# v1.net
KiCad netlist of a schematic drawn in EAGLE
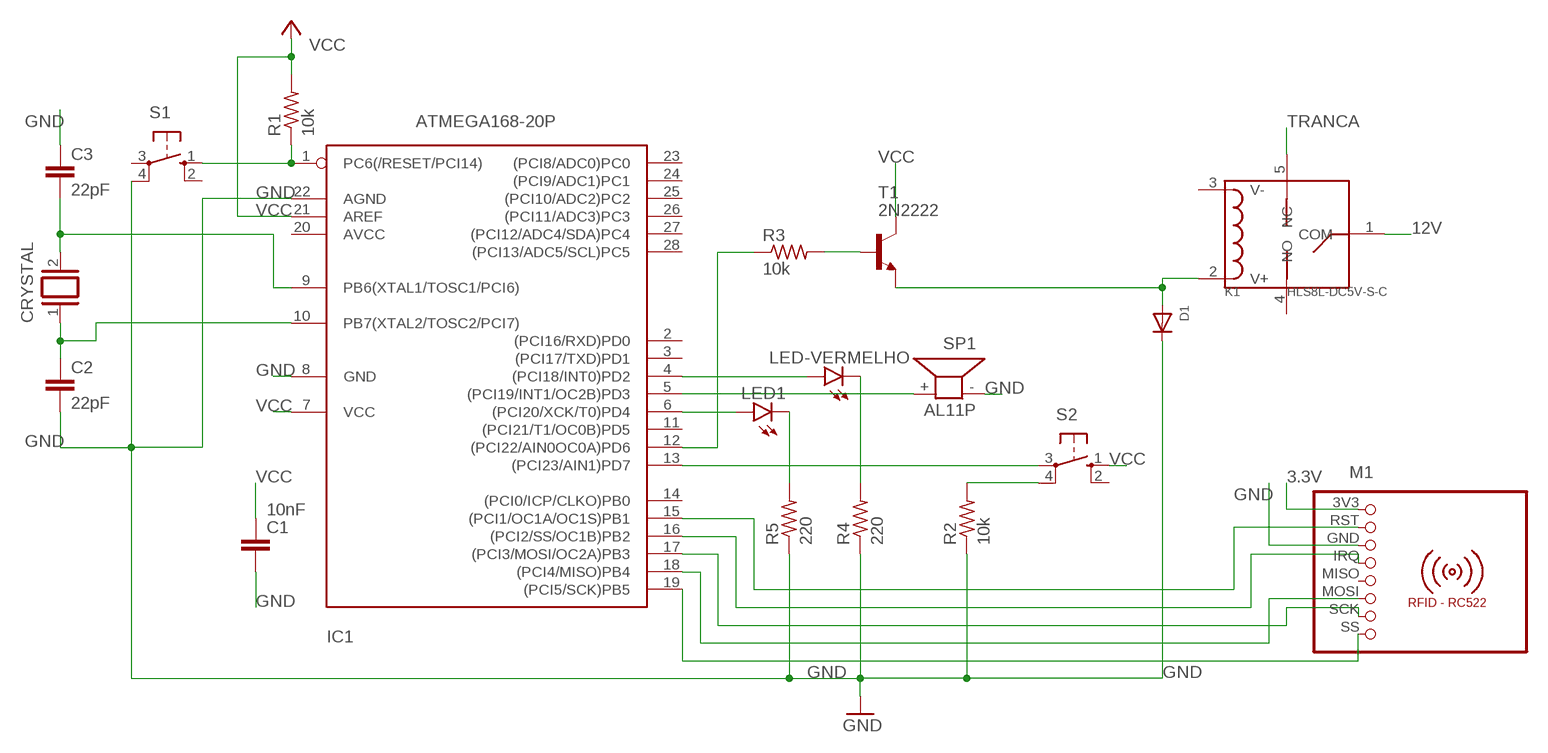
[diagram p0: schematic, sheet 1]

(export (version "E")
  (design (tool "Eeschema 10.0.6"))
  (components
    (comp (ref "C1")
      (value "10nF")
      (footprint "eagle-import:C025-025X050")
      (libsource (lib "eagle-import") (part "C-EU025-025X050"))
    )
    (comp (ref "C2")
      (value "22pF")
      (footprint "eagle-import:C025-025X050")
      (libsource (lib "eagle-import") (part "C-EU025-025X050"))
    )
    (comp (ref "C3")
      (value "22pF")
      (footprint "eagle-import:C025-025X050")
      (libsource (lib "eagle-import") (part "C-EU025-025X050"))
    )
    (comp (ref "CRYSTAL")
      (value "XTAL/S")
      (footprint "eagle-import:QS")
      (libsource (lib "eagle-import") (part "XTAL/S"))
    )
    (comp (ref "D1")
      (value "DIODEDO-1N4148")
      (footprint "eagle-import:DO-1N4148")
      (libsource (lib "eagle-import") (part "DIODEDO-1N4148"))
    )
    (comp (ref "IC1")
      (value "ATMEGA168-20P")
      (footprint "eagle-import:DIL28-3")
      (libsource (lib "eagle-import") (part "ATMEGA168P-20"))
    )
    (comp (ref "K1")
      (value "HLS8L-DC5V-S-C")
      (footprint "eagle-import:REY5-19.0X15.0X15.0MM")
      (libsource (lib "eagle-import") (part "RELAY-HLS8L-DC5V-S-C(5P-19X15MM)"))
    )
    (comp (ref "LED-VERMELHO")
      (value "LED5MM")
      (footprint "eagle-import:LED5MM")
      (libsource (lib "eagle-import") (part "LED5MM"))
    )
    (comp (ref "LED1")
      (value "LED5MM")
      (footprint "eagle-import:LED5MM")
      (libsource (lib "eagle-import") (part "LED5MM"))
    )
    (comp (ref "M1")
      (value "RFID-RC522")
      (footprint "eagle-import:RFID-RC522")
      (libsource (lib "eagle-import") (part "RFID-RC522"))
    )
    (comp (ref "R1")
      (value "10k")
      (footprint "eagle-import:0204_7")
      (libsource (lib "eagle-import") (part "R-US_0204/7"))
    )
    (comp (ref "R2")
      (value "10k")
      (footprint "eagle-import:0204_7")
      (libsource (lib "eagle-import") (part "R-US_0204/7"))
    )
    (comp (ref "R3")
      (value "10k")
      (footprint "eagle-import:0204_7")
      (libsource (lib "eagle-import") (part "R-US_0204/7"))
    )
    (comp (ref "R4")
      (value "220")
      (footprint "eagle-import:0204_7")
      (libsource (lib "eagle-import") (part "R-US_0204/7"))
    )
    (comp (ref "R5")
      (value "220")
      (footprint "eagle-import:0204_7")
      (libsource (lib "eagle-import") (part "R-US_0204/7"))
    )
    (comp (ref "S1")
      (value "10-XX")
      (footprint "eagle-import:B3F-10XX")
      (fields (field (name "MPN") "B3F-1000"))
      (libsource (lib "eagle-import") (part "10-XX"))
    )
    (comp (ref "S2")
      (value "10-XX")
      (footprint "eagle-import:B3F-10XX")
      (fields (field (name "MPN") "B3F-1000"))
      (libsource (lib "eagle-import") (part "10-XX"))
    )
    (comp (ref "SP1")
      (value "AL11P")
      (footprint "eagle-import:AL11P")
      (libsource (lib "eagle-import") (part "AL11P"))
    )
    (comp (ref "T1")
      (value "2N2222")
      (footprint "eagle-import:TO92-EBC-OVAL")
      (libsource (lib "eagle-import") (part "2N2222"))
    )
  )
  (nets
    (net (code "1") (name "/3.3V") (class "Default")
      (node (ref "M1") (pin "3V3") (pinfunction "1_3V3") (pintype "passive"))
    )
    (net (code "2") (name "/12V") (class "Default")
      (node (ref "K1") (pin "1") (pinfunction "COM_1") (pintype "bidirectional"))
    )
    (net (code "3") (name "/TRANCA") (class "Default")
      (node (ref "K1") (pin "5") (pinfunction "NC_5") (pintype "bidirectional"))
    )
    (net (code "4") (name "GND") (class "Default")
      (node (ref "C1") (pin "2") (pinfunction "2_2") (pintype "passive"))
      (node (ref "C2") (pin "2") (pinfunction "2_2") (pintype "passive"))
      (node (ref "C3") (pin "1") (pinfunction "1_1") (pintype "passive"))
      (node (ref "D1") (pin "C") (pinfunction "C_C") (pintype "passive"))
      (node (ref "IC1") (pin "22") (pinfunction "AGND_22") (pintype "bidirectional"))
      (node (ref "IC1") (pin "8") (pinfunction "GND_8") (pintype "bidirectional"))
      (node (ref "M1") (pin "GND") (pinfunction "3_GND") (pintype "passive"))
      (node (ref "R2") (pin "1") (pinfunction "1_1") (pintype "passive"))
      (node (ref "R4") (pin "1") (pinfunction "1_1") (pintype "passive"))
      (node (ref "R5") (pin "1") (pinfunction "1_1") (pintype "passive"))
      (node (ref "S1") (pin "4") (pinfunction "P1_4") (pintype "passive"))
      (node (ref "SP1") (pin "-") (pinfunction "1_-") (pintype "passive"))
    )
    (net (code "5") (name "Net-(IC1-(PCI1{slash}OC1A{slash}OC1S)PB1)") (class "Default")
      (node (ref "IC1") (pin "15") (pinfunction "(PCI1/OC1A/OC1S)PB1_15") (pintype "bidirectional"))
      (node (ref "M1") (pin "RST") (pinfunction "2_RST") (pintype "passive"))
    )
    (net (code "6") (name "Net-(IC1-(PCI2{slash}SS{slash}OC1B)PB2)") (class "Default")
      (node (ref "IC1") (pin "16") (pinfunction "(PCI2/SS/OC1B)PB2_16") (pintype "bidirectional"))
      (node (ref "M1") (pin "IRQ") (pinfunction "4_IRQ") (pintype "passive"))
    )
    (net (code "7") (name "Net-(IC1-(PCI3{slash}MOSI{slash}OC2A)PB3)") (class "Default")
      (node (ref "IC1") (pin "17") (pinfunction "(PCI3/MOSI/OC2A)PB3_17") (pintype "bidirectional"))
      (node (ref "M1") (pin "SCK") (pinfunction "7_SCK") (pintype "passive"))
    )
    (net (code "8") (name "Net-(IC1-(PCI4{slash}MISO)PB4)") (class "Default")
      (node (ref "IC1") (pin "18") (pinfunction "(PCI4/MISO)PB4_18") (pintype "bidirectional"))
      (node (ref "M1") (pin "MOSI") (pinfunction "6_MOSI") (pintype "passive"))
    )
    (net (code "9") (name "Net-(IC1-(PCI5{slash}SCK)PB5)") (class "Default")
      (node (ref "IC1") (pin "19") (pinfunction "(PCI5/SCK)PB5_19") (pintype "bidirectional"))
      (node (ref "M1") (pin "SS") (pinfunction "8_SS") (pintype "passive"))
    )
    (net (code "10") (name "Net-(IC1-(PCI18{slash}INT0)PD2)") (class "Default")
      (node (ref "IC1") (pin "4") (pinfunction "(PCI18/INT0)PD2_4") (pintype "bidirectional"))
      (node (ref "LED-VERMELHO") (pin "A") (pinfunction "A_A") (pintype "passive"))
    )
    (net (code "11") (name "Net-(IC1-(PCI19{slash}INT1{slash}OC2B)PD3)") (class "Default")
      (node (ref "IC1") (pin "5") (pinfunction "(PCI19/INT1/OC2B)PD3_5") (pintype "bidirectional"))
      (node (ref "SP1") (pin "+") (pinfunction "2_+") (pintype "passive"))
    )
    (net (code "12") (name "Net-(IC1-(PCI20{slash}XCK{slash}T0)PD4)") (class "Default")
      (node (ref "IC1") (pin "6") (pinfunction "(PCI20/XCK/T0)PD4_6") (pintype "bidirectional"))
      (node (ref "LED1") (pin "A") (pinfunction "A_A") (pintype "passive"))
    )
    (net (code "13") (name "Net-(IC1-(PCI22{slash}AIN0OC0A)PD6)") (class "Default")
      (node (ref "IC1") (pin "12") (pinfunction "(PCI22/AIN0OC0A)PD6_12") (pintype "bidirectional"))
      (node (ref "R3") (pin "1") (pinfunction "1_1") (pintype "passive"))
    )
    (net (code "14") (name "Net-(IC1-(PCI23{slash}AIN1)PD7)") (class "Default")
      (node (ref "IC1") (pin "13") (pinfunction "(PCI23/AIN1)PD7_13") (pintype "bidirectional"))
      (node (ref "S2") (pin "3") (pinfunction "P_3") (pintype "passive"))
    )
    (net (code "15") (name "Net-(IC1-PB6(XTAL1{slash}TOSC1{slash}PCI6))") (class "Default")
      (node (ref "C3") (pin "2") (pinfunction "2_2") (pintype "passive"))
      (node (ref "CRYSTAL") (pin "2") (pinfunction "2_2") (pintype "passive"))
      (node (ref "IC1") (pin "9") (pinfunction "PB6(XTAL1/TOSC1/PCI6)_9") (pintype "bidirectional"))
    )
    (net (code "16") (name "Net-(IC1-PB7(XTAL2{slash}TOSC2{slash}PCI7))") (class "Default")
      (node (ref "C2") (pin "1") (pinfunction "1_1") (pintype "passive"))
      (node (ref "CRYSTAL") (pin "1") (pinfunction "1_1") (pintype "passive"))
      (node (ref "IC1") (pin "10") (pinfunction "PB7(XTAL2/TOSC2/PCI7)_10") (pintype "bidirectional"))
    )
    (net (code "17") (name "Net-(IC1-PC6({slash}RESET{slash}PCI14))") (class "Default")
      (node (ref "IC1") (pin "1") (pinfunction "PC6(/RESET/PCI14)_1") (pintype "bidirectional"))
      (node (ref "R1") (pin "1") (pinfunction "1_1") (pintype "passive"))
      (node (ref "S1") (pin "1") (pinfunction "S_1") (pintype "passive"))
    )
    (net (code "18") (name "Net-(K1-V+)") (class "Default")
      (node (ref "D1") (pin "A") (pinfunction "A_A") (pintype "passive"))
      (node (ref "K1") (pin "2") (pinfunction "V+_2") (pintype "bidirectional"))
      (node (ref "T1") (pin "E") (pinfunction "E_E") (pintype "passive"))
    )
    (net (code "19") (name "Net-(LED-VERMELHO-C)") (class "Default")
      (node (ref "LED-VERMELHO") (pin "K") (pinfunction "C_K") (pintype "passive"))
      (node (ref "R4") (pin "2") (pinfunction "2_2") (pintype "passive"))
    )
    (net (code "20") (name "Net-(LED1-C)") (class "Default")
      (node (ref "LED1") (pin "K") (pinfunction "C_K") (pintype "passive"))
      (node (ref "R5") (pin "2") (pinfunction "2_2") (pintype "passive"))
    )
    (net (code "21") (name "Net-(R3-Pad2)") (class "Default")
      (node (ref "R3") (pin "2") (pinfunction "2_2") (pintype "passive"))
      (node (ref "T1") (pin "B") (pinfunction "B_B") (pintype "passive"))
    )
    (net (code "22") (name "Net-(S2-P1)") (class "Default")
      (node (ref "R2") (pin "2") (pinfunction "2_2") (pintype "passive"))
      (node (ref "S2") (pin "4") (pinfunction "P1_4") (pintype "passive"))
    )
    (net (code "23") (name "VCC") (class "Default")
      (node (ref "C1") (pin "1") (pinfunction "1_1") (pintype "passive"))
      (node (ref "IC1") (pin "21") (pinfunction "AREF_21") (pintype "bidirectional"))
      (node (ref "IC1") (pin "7") (pinfunction "VCC_7") (pintype "bidirectional"))
      (node (ref "R1") (pin "2") (pinfunction "2_2") (pintype "passive"))
      (node (ref "S2") (pin "1") (pinfunction "S_1") (pintype "passive"))
      (node (ref "T1") (pin "C") (pinfunction "C_C") (pintype "passive"))
    )
    (net (code "24") (name "unconnected-(IC1-(PCI0{slash}ICP{slash}CLKO)PB0-Pad14)") (class "Default")
      (node (ref "IC1") (pin "14") (pinfunction "(PCI0/ICP/CLKO)PB0_14") (pintype "bidirectional"))
    )
    (net (code "25") (name "unconnected-(IC1-(PCI8{slash}ADC0)PC0-Pad23)") (class "Default")
      (node (ref "IC1") (pin "23") (pinfunction "(PCI8/ADC0)PC0_23") (pintype "bidirectional"))
    )
    (net (code "26") (name "unconnected-(IC1-(PCI9{slash}ADC1)PC1-Pad24)") (class "Default")
      (node (ref "IC1") (pin "24") (pinfunction "(PCI9/ADC1)PC1_24") (pintype "bidirectional"))
    )
    (net (code "27") (name "unconnected-(IC1-(PCI10{slash}ADC2)PC2-Pad25)") (class "Default")
      (node (ref "IC1") (pin "25") (pinfunction "(PCI10/ADC2)PC2_25") (pintype "bidirectional"))
    )
    (net (code "28") (name "unconnected-(IC1-(PCI11{slash}ADC3)PC3-Pad26)") (class "Default")
      (node (ref "IC1") (pin "26") (pinfunction "(PCI11/ADC3)PC3_26") (pintype "bidirectional"))
    )
    (net (code "29") (name "unconnected-(IC1-(PCI12{slash}ADC4{slash}SDA)PC4-Pad27)") (class "Default")
      (node (ref "IC1") (pin "27") (pinfunction "(PCI12/ADC4/SDA)PC4_27") (pintype "bidirectional"))
    )
    (net (code "30") (name "unconnected-(IC1-(PCI13{slash}ADC5{slash}SCL)PC5-Pad28)") (class "Default")
      (node (ref "IC1") (pin "28") (pinfunction "(PCI13/ADC5/SCL)PC5_28") (pintype "bidirectional"))
    )
    (net (code "31") (name "unconnected-(IC1-(PCI16{slash}RXD)PD0-Pad2)") (class "Default")
      (node (ref "IC1") (pin "2") (pinfunction "(PCI16/RXD)PD0_2") (pintype "bidirectional"))
    )
    (net (code "32") (name "unconnected-(IC1-(PCI17{slash}TXD)PD1-Pad3)") (class "Default")
      (node (ref "IC1") (pin "3") (pinfunction "(PCI17/TXD)PD1_3") (pintype "bidirectional"))
    )
    (net (code "33") (name "unconnected-(IC1-(PCI21{slash}T1{slash}OC0B)PD5-Pad11)") (class "Default")
      (node (ref "IC1") (pin "11") (pinfunction "(PCI21/T1/OC0B)PD5_11") (pintype "bidirectional"))
    )
    (net (code "34") (name "unconnected-(IC1-AVCC-Pad20)") (class "Default")
      (node (ref "IC1") (pin "20") (pinfunction "AVCC_20") (pintype "bidirectional"))
    )
    (net (code "35") (name "unconnected-(K1-NO-Pad4)") (class "Default")
      (node (ref "K1") (pin "4") (pinfunction "NO_4") (pintype "bidirectional"))
    )
    (net (code "36") (name "unconnected-(K1-V--Pad3)") (class "Default")
      (node (ref "K1") (pin "3") (pinfunction "V-_3") (pintype "bidirectional"))
    )
    (net (code "37") (name "unconnected-(M1-5-PadMISO)") (class "Default")
      (node (ref "M1") (pin "MISO") (pinfunction "5_MISO") (pintype "passive"))
    )
    (net (code "38") (name "unconnected-(S1-P-Pad3)") (class "Default")
      (node (ref "S1") (pin "3") (pinfunction "P_3") (pintype "passive"))
    )
    (net (code "39") (name "unconnected-(S1-S1-Pad2)") (class "Default")
      (node (ref "S1") (pin "2") (pinfunction "S1_2") (pintype "passive"))
    )
    (net (code "40") (name "unconnected-(S2-S1-Pad2)") (class "Default")
      (node (ref "S2") (pin "2") (pinfunction "S1_2") (pintype "passive"))
    )
  )
)
